# Carrier_Board.net
KiCad netlist of a schematic drawn in EAGLE
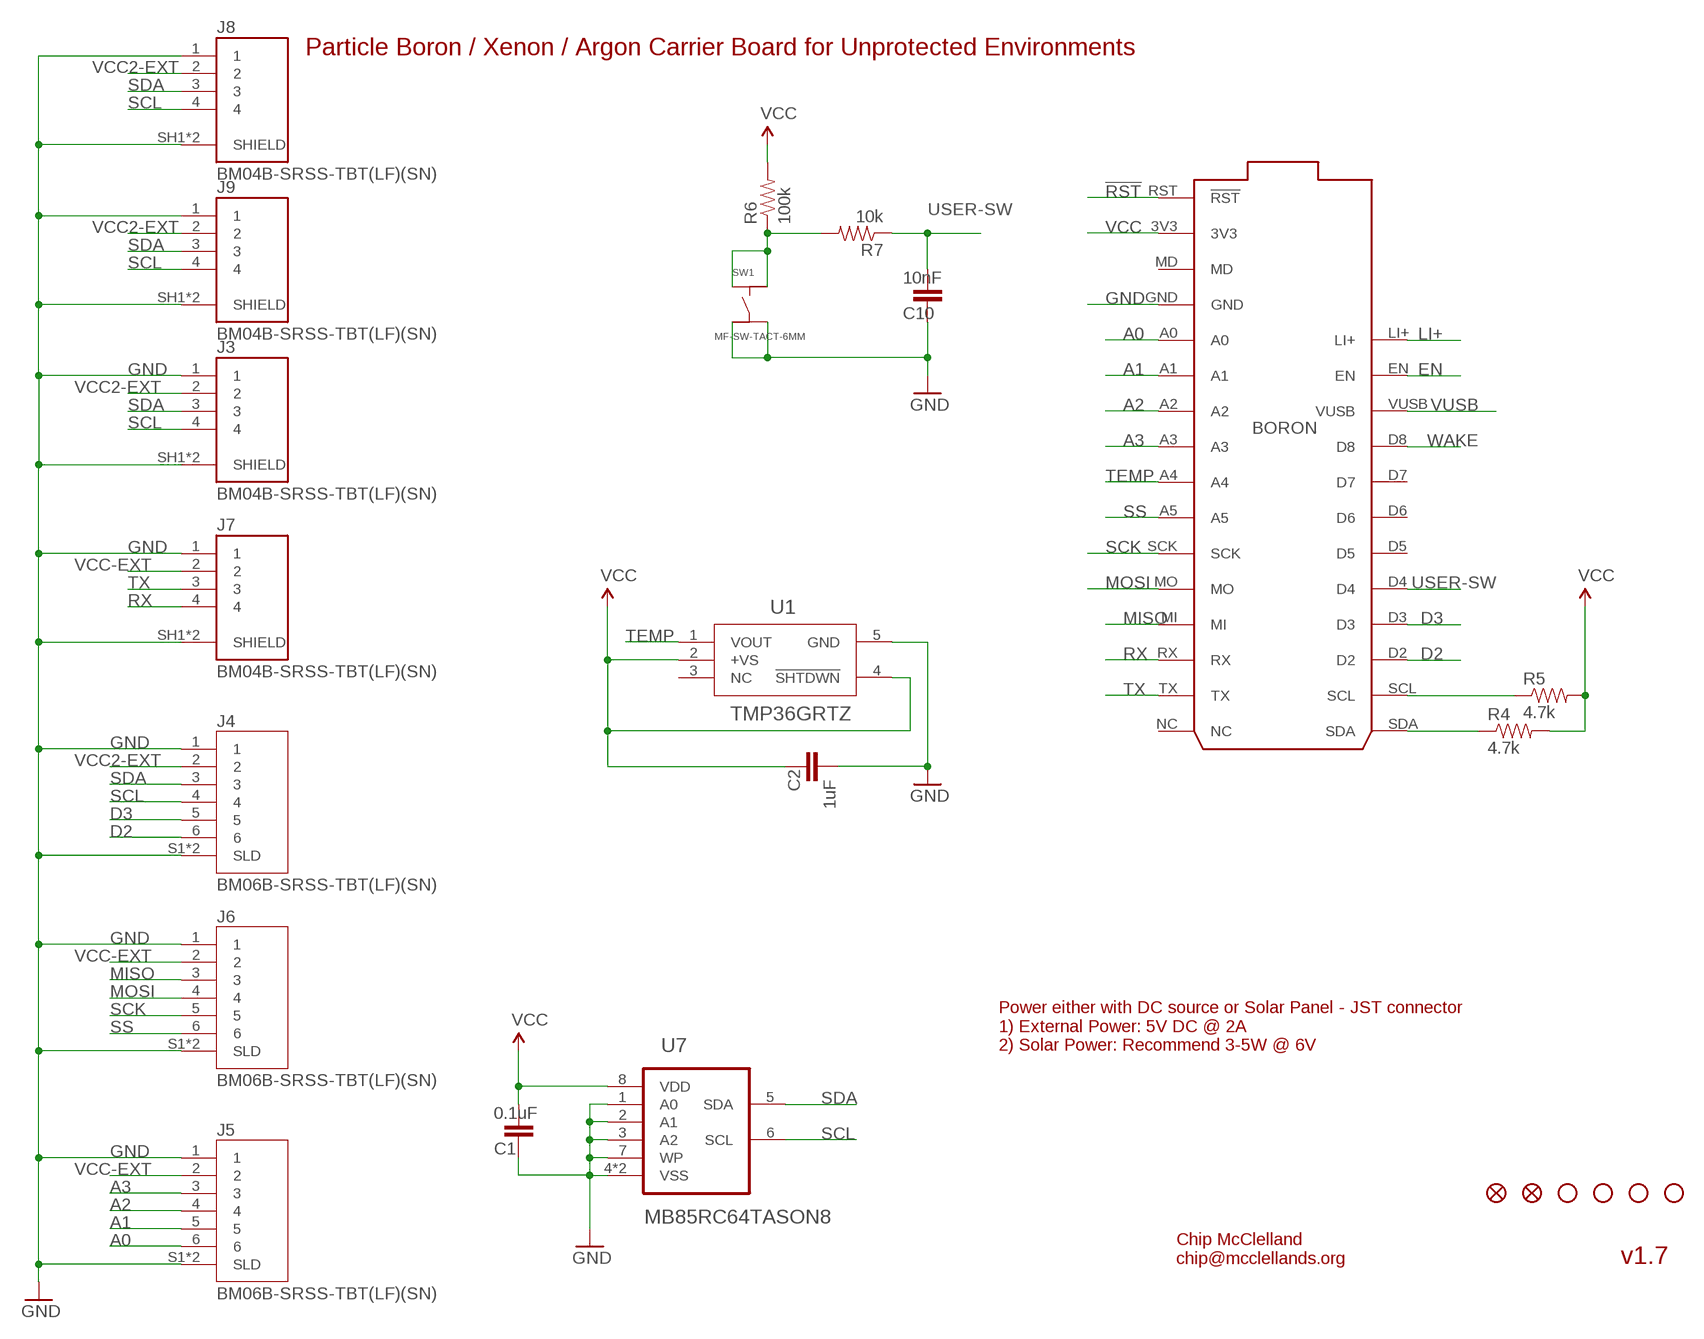
[diagram p0: schematic, sheet 1]
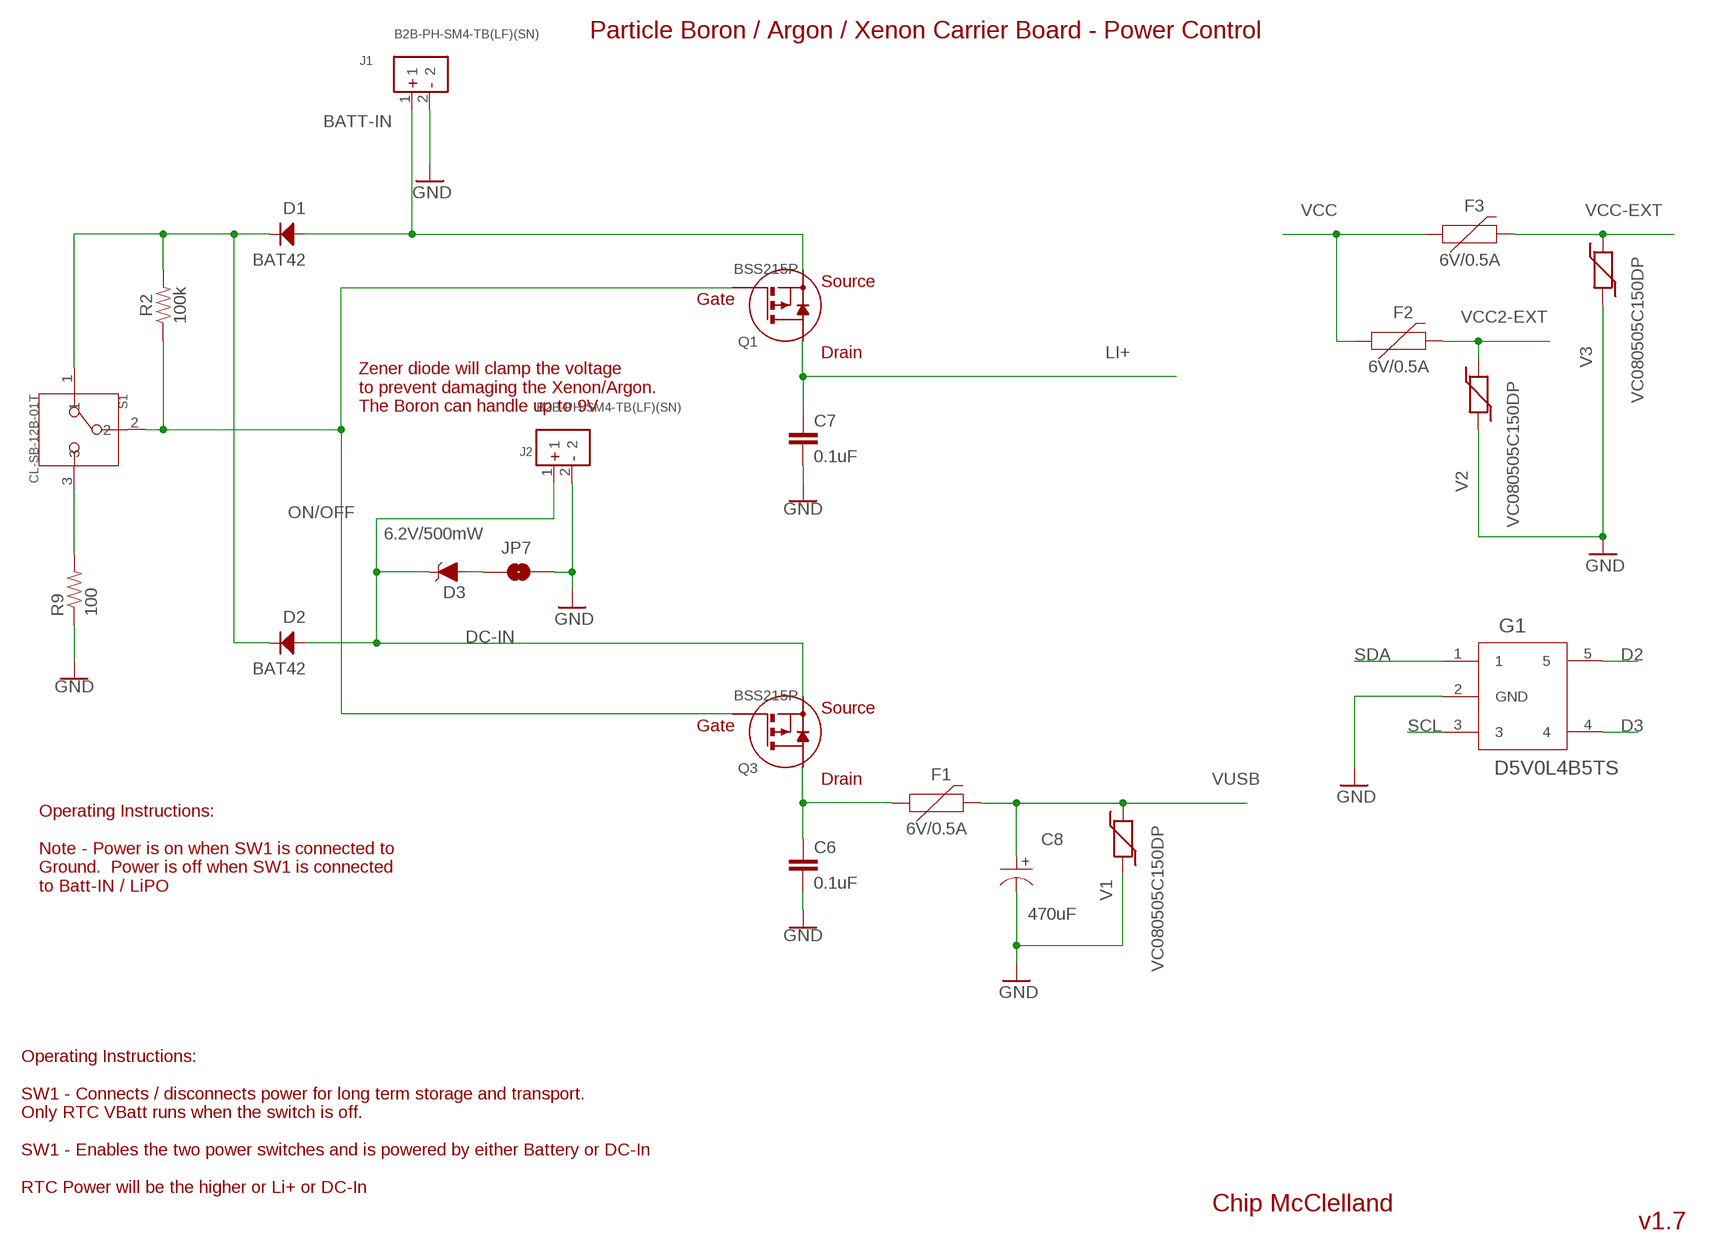
[diagram p1: schematic, sheet 2]
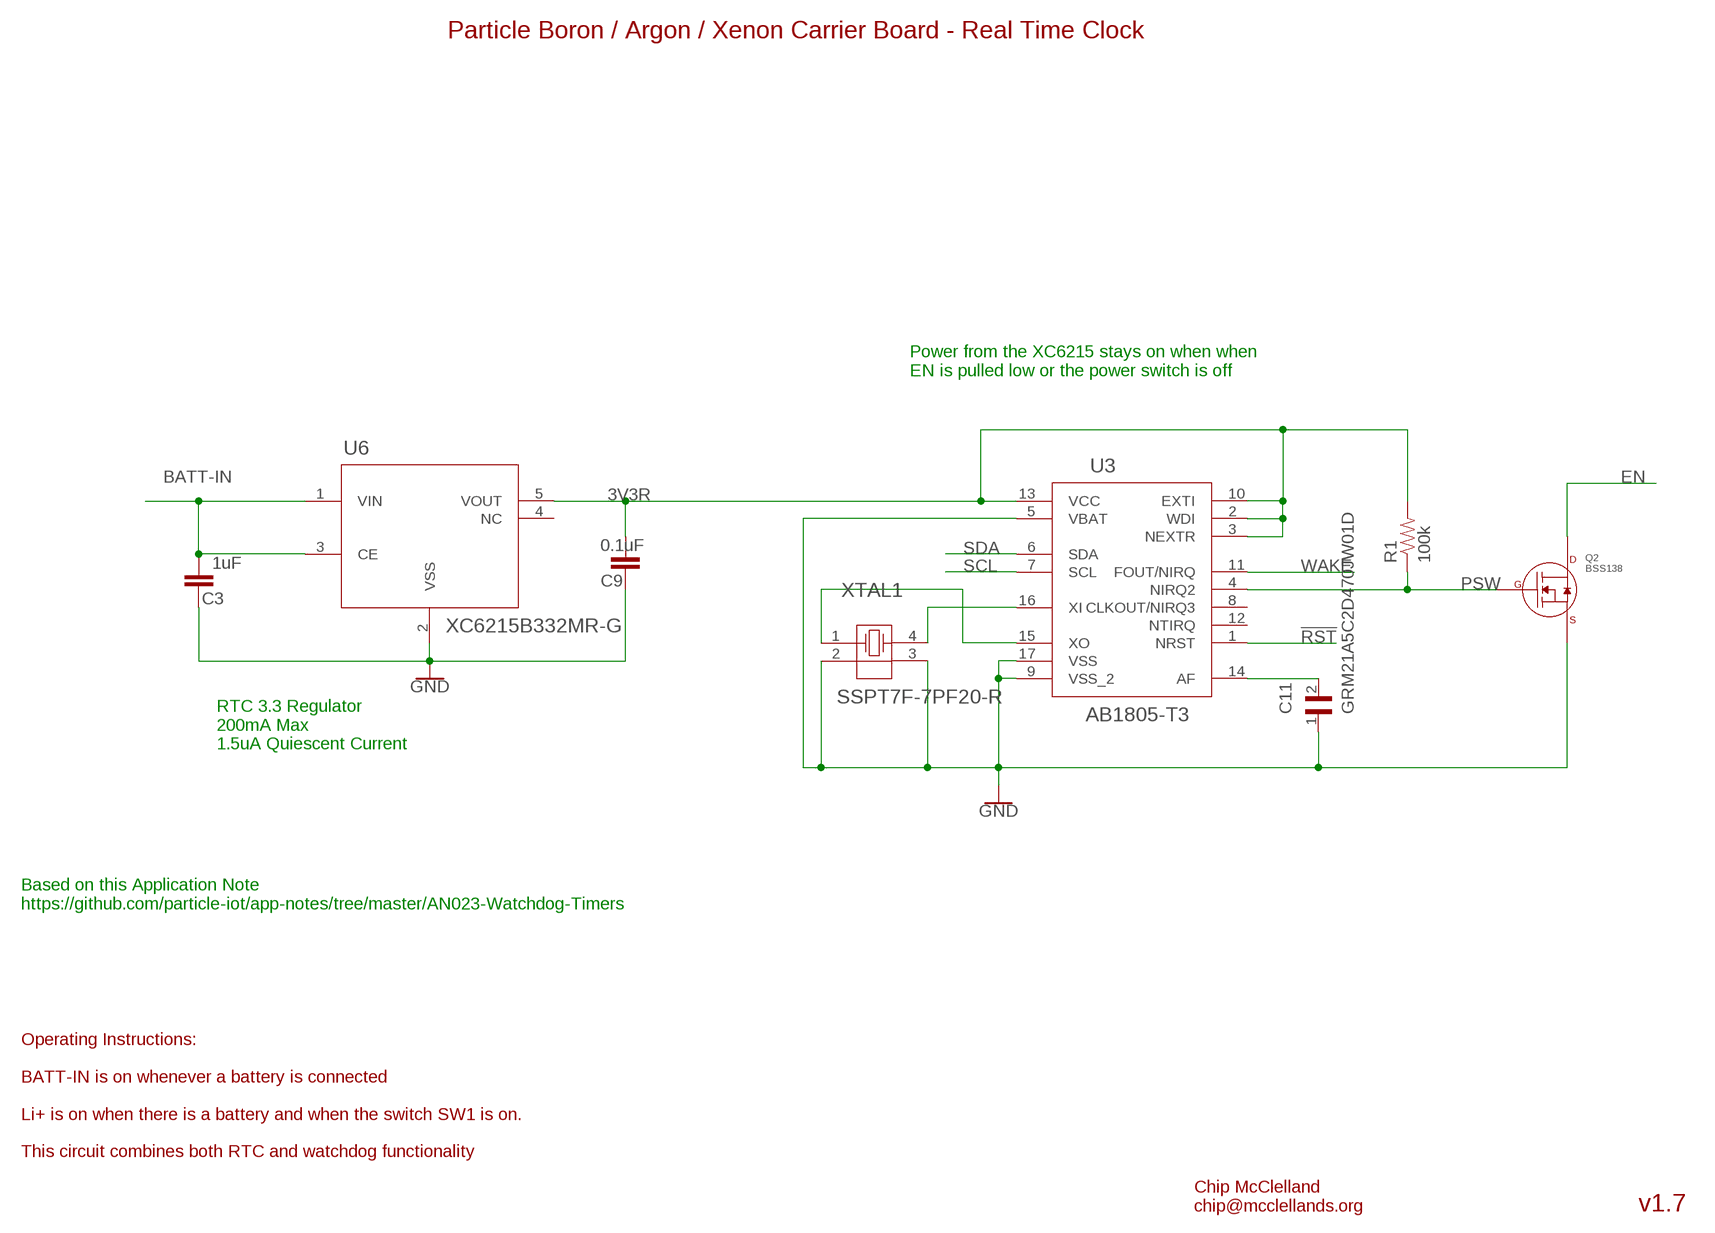
[diagram p2: schematic, sheet 3]
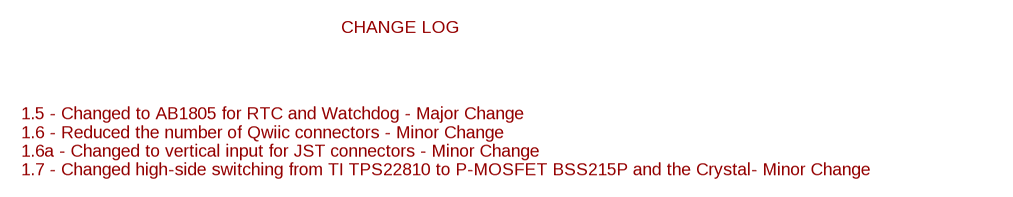
[diagram p3: schematic, sheet 4]

(export (version "E")
  (design (tool "Eeschema 10.0.6"))
  (components
    (comp (ref "C3")
      (value "1uF")
      (footprint "eagle-import:0805@1")
      (fields
        (field (name "HOUSEPART") "yes")
        (field (name "MPN") "MF-CAP-0805-1uF")
        (field (name "MPN_1") "MF-CAP-0805-1uF")
      )
      (libsource (lib "eagle-import") (part "CAP-MF-1UF-0805"))
    )
    (comp (ref "C9")
      (value "0.1uF")
      (footprint "eagle-import:0805@1")
      (fields
        (field (name "HOUSEPART") "YES")
        (field (name "MPN") "MF-CAP-0805-0.1uF")
        (field (name "HOUSEPART_1") "YES")
        (field (name "MPN_1") "MF-CAP-0805-0.1uF")
        (field (name "POPULATE") "1")
      )
      (libsource (lib "eagle-import") (part "CAP-MF-0.1UF-0805"))
    )
    (comp (ref "C11")
      (value "GRM21A5C2D470JW01D")
      (footprint "eagle-import:CAPC2012X100N")
      (fields (field (name "DIGI-KEY_PART_NUMBER") "490-14653-1-ND") (field (name "MF") "Murata"))
      (libsource (lib "eagle-import") (part "GRM21A5C2D470JW01D"))
    )
    (comp (ref "Q2")
      (value "BSS138")
      (footprint "eagle-import:SOT-23_3L_ONS")
      (fields
        (field (name "MPN") "MF-DSC-SOT233-BSS138")
        (field (name "COPYRIGHT") "Copyright (C) 2018 Accelerated Designs. All rights reserved")
      )
      (libsource (lib "eagle-import") (part "BSS138"))
    )
    (comp (ref "R1")
      (value "100k")
      (footprint "eagle-import:0805")
      (fields
        (field (name "MPN") "MF-RES-0805-100K")
        (field (name "HOUSEPART") "YES")
        (field (name "MPN_1") "MF-RES-0805-100K")
      )
      (libsource (lib "eagle-import") (part "RESISTOR-MF-100K-0805"))
    )
    (comp (ref "U3")
      (value "AB1805-T3")
      (footprint "eagle-import:QFN_16_ABR")
      (fields (field (name "MANUFACTURER") "Abracon LLC"))
      (libsource (lib "eagle-import") (part "AB1805-T3"))
    )
    (comp (ref "U6")
      (value "XC6215B332MR-G")
      (footprint "eagle-import:SOT-25_TOR")
      (libsource (lib "eagle-import") (part "XC6215B332MR-G"))
    )
    (comp (ref "XTAL1")
      (value "SSPT7F-7PF20-R")
      (footprint "eagle-import:SSP-T7-F_EPS")
      (fields (field (name "COPYRIGHT") "Copyright (C) 2018 Accelerated Designs. All rights reserved"))
      (libsource (lib "eagle-import") (part "SSPT7F-7PF20-R"))
    )
    (comp (ref "C1")
      (value "0.1uF")
      (footprint "eagle-import:0805@1")
      (fields
        (field (name "HOUSEPART") "YES")
        (field (name "MPN") "MF-CAP-0805-0.1uF")
        (field (name "HOUSEPART_1") "YES")
        (field (name "MPN_1") "MF-CAP-0805-0.1uF")
        (field (name "POPULATE") "1")
      )
      (libsource (lib "eagle-import") (part "CAP-MF-0.1UF-0805"))
    )
    (comp (ref "C2")
      (value "1uF")
      (footprint "eagle-import:0805@1")
      (fields
        (field (name "HOUSEPART") "yes")
        (field (name "MPN") "MF-CAP-0805-1uF")
        (field (name "MPN_1") "MF-CAP-0805-1uF")
      )
      (libsource (lib "eagle-import") (part "CAP-MF-1UF-0805"))
    )
    (comp (ref "C10")
      (value "10nF")
      (footprint "eagle-import:0805@1")
      (fields
        (field (name "HOUSEPART") "NO")
        (field (name "MPN") "C0805X103K1RAC3316")
        (field (name "HOUSEPART_1") "No")
        (field (name "MPN_1") "08051C103K4T2A")
        (field (name "POPULATE") "1")
      )
      (libsource (lib "eagle-import") (part "CAP-10NF-0805"))
    )
    (comp (ref "FD1")
      (value "FIDUCIALUFIDUCIAL")
      (footprint "eagle-import:FIDUCIAL-MICRO")
      (libsource (lib "eagle-import") (part "FIDUCIALUFIDUCIAL"))
    )
    (comp (ref "FD2")
      (value "FIDUCIALUFIDUCIAL")
      (footprint "eagle-import:FIDUCIAL-MICRO")
      (libsource (lib "eagle-import") (part "FIDUCIALUFIDUCIAL"))
    )
    (comp (ref "J3")
      (value "BM04B-SRSS-TBT(LF)(SN)")
      (footprint "eagle-import:CONN_BM04B-SRSS-TBT(LF)(SN)")
      (fields (field (name "MF") "JST Sales"))
      (libsource (lib "eagle-import") (part "BM04B-SRSS-TBT(LF)(SN)"))
    )
    (comp (ref "J4")
      (value "BM06B-SRSS-TBT(LF)(SN)")
      (footprint "eagle-import:JST_BM06B-SRSS-TB(LF)(SN)")
      (libsource (lib "eagle-import") (part "BM06B-SRSS-TBT(LF)(SN)"))
    )
    (comp (ref "J5")
      (value "BM06B-SRSS-TBT(LF)(SN)")
      (footprint "eagle-import:JST_BM06B-SRSS-TB(LF)(SN)")
      (libsource (lib "eagle-import") (part "BM06B-SRSS-TBT(LF)(SN)"))
    )
    (comp (ref "J6")
      (value "BM06B-SRSS-TBT(LF)(SN)")
      (footprint "eagle-import:JST_BM06B-SRSS-TB(LF)(SN)")
      (libsource (lib "eagle-import") (part "BM06B-SRSS-TBT(LF)(SN)"))
    )
    (comp (ref "J7")
      (value "BM04B-SRSS-TBT(LF)(SN)")
      (footprint "eagle-import:CONN_BM04B-SRSS-TBT(LF)(SN)")
      (fields (field (name "MF") "JST Sales"))
      (libsource (lib "eagle-import") (part "BM04B-SRSS-TBT(LF)(SN)"))
    )
    (comp (ref "J8")
      (value "BM04B-SRSS-TBT(LF)(SN)")
      (footprint "eagle-import:CONN_BM04B-SRSS-TBT(LF)(SN)")
      (fields (field (name "MF") "JST Sales"))
      (libsource (lib "eagle-import") (part "BM04B-SRSS-TBT(LF)(SN)"))
    )
    (comp (ref "J9")
      (value "BM04B-SRSS-TBT(LF)(SN)")
      (footprint "eagle-import:CONN_BM04B-SRSS-TBT(LF)(SN)")
      (fields (field (name "MF") "JST Sales"))
      (libsource (lib "eagle-import") (part "BM04B-SRSS-TBT(LF)(SN)"))
    )
    (comp (ref "JP3")
      (value "STAND-OFF")
      (footprint "eagle-import:STAND-OFF")
      (libsource (lib "eagle-import") (part "STAND-OFF"))
    )
    (comp (ref "JP4")
      (value "STAND-OFF")
      (footprint "eagle-import:STAND-OFF")
      (libsource (lib "eagle-import") (part "STAND-OFF"))
    )
    (comp (ref "JP5")
      (value "STAND-OFF")
      (footprint "eagle-import:STAND-OFF")
      (libsource (lib "eagle-import") (part "STAND-OFF"))
    )
    (comp (ref "JP6")
      (value "STAND-OFF")
      (footprint "eagle-import:STAND-OFF")
      (libsource (lib "eagle-import") (part "STAND-OFF"))
    )
    (comp (ref "P1")
      (value "Particle Boron / Xenon / Argon")
      (footprint "eagle-import:PARTICLE-DEVICES_BORON")
      (libsource (lib "eagle-import") (part "PARTICLE-DEVICES-BORON"))
    )
    (comp (ref "R4")
      (value "4.7k")
      (footprint "eagle-import:0805")
      (fields
        (field (name "HOUSEPART") "1")
        (field (name "MPN") "MF-RES-0805-4.7K")
        (field (name "MPN_1") "MF-RES-0805-4.7K")
      )
      (libsource (lib "eagle-import") (part "RESISTOR-MF-4.7K-0805"))
    )
    (comp (ref "R5")
      (value "4.7k")
      (footprint "eagle-import:0805")
      (fields
        (field (name "HOUSEPART") "1")
        (field (name "MPN") "MF-RES-0805-4.7K")
        (field (name "MPN_1") "MF-RES-0805-4.7K")
      )
      (libsource (lib "eagle-import") (part "RESISTOR-MF-4.7K-0805"))
    )
    (comp (ref "R6")
      (value "100k")
      (footprint "eagle-import:0805")
      (fields
        (field (name "MPN") "MF-RES-0805-100K")
        (field (name "HOUSEPART") "YES")
        (field (name "MPN_1") "MF-RES-0805-100K")
      )
      (libsource (lib "eagle-import") (part "RESISTOR-MF-100K-0805"))
    )
    (comp (ref "R7")
      (value "10k")
      (footprint "eagle-import:0805")
      (fields
        (field (name "MPN") "MF-RES-0805-10K")
        (field (name "HOUSEPART") "YES")
        (field (name "MPN_1") "MF-RES-0805-10K")
      )
      (libsource (lib "eagle-import") (part "RESISTOR-MF-10K-0805"))
    )
    (comp (ref "SW1")
      (value "MF-SW-TACT-6MM")
      (footprint "eagle-import:TACT6MM")
      (fields (field (name "HOUSEPART") "YES"))
      (libsource (lib "eagle-import") (part "TACT_6MM"))
    )
    (comp (ref "U1")
      (value "TMP36GRTZ")
      (footprint "eagle-import:RJ_5_ADI")
      (fields
        (field (name "MANUFACTURER_PART_NUMBER") "TMP36GRTZ-REEL7")
        (field (name "MANUFACTURER_PART_NUMBER_1") "TMP36GRTZ-REEL7")
      )
      (libsource (lib "eagle-import") (part "TMP36GRTZ-REEL7"))
    )
    (comp (ref "U7")
      (value "MB85RC64TASON8")
      (footprint "eagle-import:SON50P200X300X75-9N")
      (libsource (lib "eagle-import") (part "MB85RC64TASON8"))
    )
    (comp (ref "C6")
      (value "0.1uF")
      (footprint "eagle-import:0805@1")
      (fields
        (field (name "HOUSEPART") "YES")
        (field (name "MPN") "MF-CAP-0805-0.1uF")
        (field (name "HOUSEPART_1") "Yes")
        (field (name "MPN_1") "MF-CAP-0805-0.1uF")
      )
      (libsource (lib "eagle-import") (part "CAP-MF-0.1UF-0805"))
    )
    (comp (ref "C7")
      (value "0.1uF")
      (footprint "eagle-import:0805@1")
      (fields
        (field (name "HOUSEPART") "YES")
        (field (name "MPN") "MF-CAP-0805-0.1uF")
        (field (name "HOUSEPART_1") "Yes")
        (field (name "MPN_1") "MF-CAP-0805-0.1uF")
      )
      (libsource (lib "eagle-import") (part "CAP-MF-0.1UF-0805"))
    )
    (comp (ref "C8")
      (value "470uF")
      (footprint "eagle-import:CP10MM")
      (fields (field (name "HOUSEPART") "1") (field (name "MPN") "MF-CAP-10MM-470uF"))
      (libsource (lib "eagle-import") (part "CAPACITOR_P_10MM"))
    )
    (comp (ref "D1")
      (value "BAT42")
      (footprint "eagle-import:SOD-123")
      (fields (field (name "HOUSEPART") "YES") (field (name "MPN") "MF-DIO-SOD123-BAT42"))
      (libsource (lib "eagle-import") (part "DIODES_SOD-123_BAT42"))
    )
    (comp (ref "D2")
      (value "BAT42")
      (footprint "eagle-import:SOD-123")
      (fields (field (name "HOUSEPART") "YES") (field (name "MPN") "MF-DIO-SOD123-BAT42"))
      (libsource (lib "eagle-import") (part "DIODES_SOD-123_BAT42"))
    )
    (comp (ref "D3")
      (value "6.2V/500mW")
      (footprint "eagle-import:PANASONIC_SMINI2-F5-B")
      (fields (field (name "MPN") "TDZ6V2J,115"))
      (libsource (lib "eagle-import") (part "DIODE-ZENER-DZ2J150M0L"))
    )
    (comp (ref "F1")
      (value "6V/0.5A")
      (footprint "eagle-import:1206")
      (fields (field (name "MPN") "046801.5NR"))
      (libsource (lib "eagle-import") (part "PPTC_HALF-AMP"))
    )
    (comp (ref "F2")
      (value "6V/0.5A")
      (footprint "eagle-import:1206")
      (fields (field (name "MPN") "0466.500NR"))
      (libsource (lib "eagle-import") (part "PPTC_HALF-AMP"))
    )
    (comp (ref "F3")
      (value "6V/0.5A")
      (footprint "eagle-import:1206")
      (fields (field (name "MPN") "0466.500NR"))
      (libsource (lib "eagle-import") (part "PPTC_HALF-AMP"))
    )
    (comp (ref "G1")
      (value "D5V0L4B5TS")
      (footprint "eagle-import:SOT-23-5")
      (fields (field (name "MPN") "D5V0L4B5TS-7"))
      (libsource (lib "eagle-import") (part "D5V0L4B5TS"))
    )
    (comp (ref "J1")
      (value "B2B-PH-SM4-TB(LF)(SN)")
      (footprint "eagle-import:JST_B2B-PH-SM4-TB(LF)(SN)")
      (fields (field (name "DIGI-KEY_PART_NUMBER") "455-1734-1-ND") (field (name "MF") "JST Sales"))
      (libsource (lib "eagle-import") (part "B2B-PH-SM4-TB(LF)(SN)"))
    )
    (comp (ref "J2")
      (value "B2B-PH-SM4-TB(LF)(SN)")
      (footprint "eagle-import:JST_B2B-PH-SM4-TB(LF)(SN)")
      (fields (field (name "DIGI-KEY_PART_NUMBER") "455-1734-1-ND") (field (name "MF") "JST Sales"))
      (libsource (lib "eagle-import") (part "B2B-PH-SM4-TB(LF)(SN)"))
    )
    (comp (ref "JP7")
      (value "JUMPER-SMT_2_NO_SILK")
      (footprint "eagle-import:SMT-JUMPER_2_NO_SILK")
      (libsource (lib "eagle-import") (part "JUMPER-SMT_2_NO_SILK"))
    )
    (comp (ref "Q1")
      (value "BSS215P")
      (footprint "eagle-import:SOT-23_3L_ONS-M")
      (fields (field (name "HOUSEPART") "No") (field (name "MPN") "BSS215PH6327XTSA1"))
      (libsource (lib "eagle-import") (part "BSS215P"))
    )
    (comp (ref "Q3")
      (value "BSS215P")
      (footprint "eagle-import:SOT-23_3L_ONS-M")
      (fields (field (name "HOUSEPART") "No") (field (name "MPN") "BSS215PH6327XTSA1"))
      (libsource (lib "eagle-import") (part "BSS215P"))
    )
    (comp (ref "R2")
      (value "100k")
      (footprint "eagle-import:0805")
      (fields (field (name "MPN") "MF-RES-0805-100K"))
      (libsource (lib "eagle-import") (part "RESISTOR-MF-100K-0805"))
    )
    (comp (ref "R9")
      (value "100")
      (footprint "eagle-import:0805")
      (fields
        (field (name "HOUSEPART") "YES")
        (field (name "MPN") "MF-RES-0805-100")
        (field (name "HOUSEPART_1") "Yes")
        (field (name "MPN_1") "MF-RES-0805-100")
      )
      (libsource (lib "eagle-import") (part "RESISTOR-MF-100-0805"))
    )
    (comp (ref "S1")
      (value "CL-SB-12B-01T")
      (footprint "eagle-import:CL-SB-12B")
      (fields (field (name "DIGI-KEY_PART_NUMBER") "563-1318-1-ND") (field (name "MF") "Nidec Copal"))
      (libsource (lib "eagle-import") (part "CL-SB-12B-01T"))
    )
    (comp (ref "V1")
      (value "VC080505C150DP")
      (footprint "eagle-import:0805")
      (libsource (lib "eagle-import") (part "VARISTOR"))
    )
    (comp (ref "V2")
      (value "VC080505C150DP")
      (footprint "eagle-import:0805")
      (libsource (lib "eagle-import") (part "VARISTOR"))
    )
    (comp (ref "V3")
      (value "VC080505C150DP")
      (footprint "eagle-import:0805")
      (libsource (lib "eagle-import") (part "VARISTOR"))
    )
  )
  (nets
    (net (code "1") (name "3V3R") (class "Default")
      (node (ref "C9") (pin "1") (pinfunction "1_1") (pintype "passive"))
      (node (ref "R1") (pin "2") (pinfunction "2_2") (pintype "passive"))
      (node (ref "U3") (pin "10") (pinfunction "EXTI_10") (pintype "input"))
      (node (ref "U3") (pin "13") (pinfunction "VCC_13") (pintype "power_in"))
      (node (ref "U3") (pin "2") (pinfunction "WDI_2") (pintype "input"))
      (node (ref "U3") (pin "3") (pinfunction "NEXTR_3") (pintype "input"))
      (node (ref "U6") (pin "5") (pinfunction "VOUT_5") (pintype "output"))
    )
    (net (code "2") (name "A0") (class "Default")
      (node (ref "J5") (pin "6") (pinfunction "6_6") (pintype "passive"))
      (node (ref "P1") (pin "A0") (pinfunction "A0_A0") (pintype "bidirectional"))
    )
    (net (code "3") (name "A1") (class "Default")
      (node (ref "J5") (pin "5") (pinfunction "5_5") (pintype "passive"))
      (node (ref "P1") (pin "A1") (pinfunction "A1_A1") (pintype "bidirectional"))
    )
    (net (code "4") (name "A2") (class "Default")
      (node (ref "J5") (pin "4") (pinfunction "4_4") (pintype "passive"))
      (node (ref "P1") (pin "A2") (pinfunction "A2_A2") (pintype "bidirectional"))
    )
    (net (code "5") (name "A3") (class "Default")
      (node (ref "J5") (pin "3") (pinfunction "3_3") (pintype "passive"))
      (node (ref "P1") (pin "A3") (pinfunction "A3_A3") (pintype "bidirectional"))
    )
    (net (code "6") (name "BATT-IN") (class "Default")
      (node (ref "C3") (pin "2") (pinfunction "2_2") (pintype "passive"))
      (node (ref "D1") (pin "ANODE") (pinfunction "ANODE_ANODE") (pintype "bidirectional"))
      (node (ref "J1") (pin "1") (pinfunction "1_1") (pintype "passive"))
      (node (ref "Q1") (pin "2") (pinfunction "SOURCE_2") (pintype "passive"))
      (node (ref "U6") (pin "1") (pinfunction "VIN_1") (pintype "power_in"))
      (node (ref "U6") (pin "3") (pinfunction "CE_3") (pintype "passive"))
    )
    (net (code "7") (name "D2") (class "Default")
      (node (ref "G1") (pin "5") (pinfunction "5_5") (pintype "output"))
      (node (ref "J4") (pin "6") (pinfunction "6_6") (pintype "passive"))
      (node (ref "P1") (pin "D2") (pinfunction "D2_D2") (pintype "bidirectional"))
    )
    (net (code "8") (name "D3") (class "Default")
      (node (ref "G1") (pin "4") (pinfunction "4_4") (pintype "output"))
      (node (ref "J4") (pin "5") (pinfunction "5_5") (pintype "passive"))
      (node (ref "P1") (pin "D3") (pinfunction "D3_D3") (pintype "bidirectional"))
    )
    (net (code "9") (name "DC-IN") (class "Default")
      (node (ref "D2") (pin "ANODE") (pinfunction "ANODE_ANODE") (pintype "bidirectional"))
      (node (ref "D3") (pin "C") (pinfunction "C_C") (pintype "passive"))
      (node (ref "J2") (pin "1") (pinfunction "1_1") (pintype "passive"))
      (node (ref "Q3") (pin "2") (pinfunction "SOURCE_2") (pintype "passive"))
    )
    (net (code "10") (name "EN") (class "Default")
      (node (ref "P1") (pin "EN") (pinfunction "EN_EN") (pintype "bidirectional"))
      (node (ref "Q2") (pin "3") (pinfunction "DRAIN_3") (pintype "bidirectional"))
    )
    (net (code "11") (name "GND") (class "Default")
      (node (ref "C1") (pin "2") (pinfunction "2_2") (pintype "passive"))
      (node (ref "C10") (pin "2") (pinfunction "2_2") (pintype "passive"))
      (node (ref "C11") (pin "1") (pinfunction "1_1") (pintype "passive"))
      (node (ref "C2") (pin "2") (pinfunction "2_2") (pintype "passive"))
      (node (ref "C3") (pin "1") (pinfunction "1_1") (pintype "passive"))
      (node (ref "C6") (pin "2") (pinfunction "2_2") (pintype "passive"))
      (node (ref "C7") (pin "2") (pinfunction "2_2") (pintype "passive"))
      (node (ref "C8") (pin "P$2") (pinfunction "P$2_P$2") (pintype "passive"))
      (node (ref "C9") (pin "2") (pinfunction "2_2") (pintype "passive"))
      (node (ref "G1") (pin "2") (pinfunction "GND_2") (pintype "power_in"))
      (node (ref "J1") (pin "2") (pinfunction "2_2") (pintype "passive"))
      (node (ref "J2") (pin "2") (pinfunction "2_2") (pintype "passive"))
      (node (ref "J3") (pin "1") (pinfunction "1_1") (pintype "passive"))
      (node (ref "J3") (pin "SH1") (pinfunction "SHIELD_SH1") (pintype "passive"))
      (node (ref "J3") (pin "SH2") (pinfunction "SHIELD_SH2") (pintype "passive"))
      (node (ref "J4") (pin "1") (pinfunction "1_1") (pintype "passive"))
      (node (ref "J4") (pin "S1") (pinfunction "SLD_S1") (pintype "passive"))
      (node (ref "J4") (pin "S2") (pinfunction "SLD_S2") (pintype "passive"))
      (node (ref "J5") (pin "1") (pinfunction "1_1") (pintype "passive"))
      (node (ref "J5") (pin "S1") (pinfunction "SLD_S1") (pintype "passive"))
      (node (ref "J5") (pin "S2") (pinfunction "SLD_S2") (pintype "passive"))
      (node (ref "J6") (pin "1") (pinfunction "1_1") (pintype "passive"))
      (node (ref "J6") (pin "S1") (pinfunction "SLD_S1") (pintype "passive"))
      (node (ref "J6") (pin "S2") (pinfunction "SLD_S2") (pintype "passive"))
      (node (ref "J7") (pin "1") (pinfunction "1_1") (pintype "passive"))
      (node (ref "J7") (pin "SH1") (pinfunction "SHIELD_SH1") (pintype "passive"))
      (node (ref "J7") (pin "SH2") (pinfunction "SHIELD_SH2") (pintype "passive"))
      (node (ref "J8") (pin "1") (pinfunction "1_1") (pintype "passive"))
      (node (ref "J8") (pin "SH1") (pinfunction "SHIELD_SH1") (pintype "passive"))
      (node (ref "J8") (pin "SH2") (pinfunction "SHIELD_SH2") (pintype "passive"))
      (node (ref "J9") (pin "1") (pinfunction "1_1") (pintype "passive"))
      (node (ref "J9") (pin "SH1") (pinfunction "SHIELD_SH1") (pintype "passive"))
      (node (ref "J9") (pin "SH2") (pinfunction "SHIELD_SH2") (pintype "passive"))
      (node (ref "JP7") (pin "1") (pinfunction "1_1") (pintype "passive"))
      (node (ref "P1") (pin "GND") (pinfunction "GND_GND") (pintype "bidirectional"))
      (node (ref "Q2") (pin "2") (pinfunction "SOURCE_2") (pintype "bidirectional"))
      (node (ref "R9") (pin "1") (pinfunction "1_1") (pintype "passive"))
      (node (ref "SW1") (pin "P$3") (pinfunction "P$3_P$3") (pintype "bidirectional"))
      (node (ref "SW1") (pin "P$4") (pinfunction "P$4_P$4") (pintype "bidirectional"))
      (node (ref "U1") (pin "5") (pinfunction "GND_5") (pintype "passive"))
      (node (ref "U3") (pin "17") (pinfunction "VSS_17") (pintype "power_in"))
      (node (ref "U3") (pin "5") (pinfunction "VBAT_5") (pintype "power_in"))
      (node (ref "U3") (pin "9") (pinfunction "VSS_2_9") (pintype "power_in"))
      (node (ref "U6") (pin "2") (pinfunction "VSS_2") (pintype "passive"))
      (node (ref "U7") (pin "1") (pinfunction "A0_1") (pintype "input"))
      (node (ref "U7") (pin "2") (pinfunction "A1_2") (pintype "input"))
      (node (ref "U7") (pin "3") (pinfunction "A2_3") (pintype "input"))
      (node (ref "U7") (pin "4") (pinfunction "VSS_4") (pintype "passive"))
      (node (ref "U7") (pin "7") (pinfunction "WP_7") (pintype "input"))
      (node (ref "U7") (pin "9") (pinfunction "VSS_9") (pintype "passive"))
      (node (ref "V1") (pin "1") (pinfunction "1_1") (pintype "passive"))
      (node (ref "V2") (pin "1") (pinfunction "1_1") (pintype "passive"))
      (node (ref "V3") (pin "1") (pinfunction "1_1") (pintype "passive"))
      (node (ref "XTAL1") (pin "2") (pinfunction "2_2") (pintype "passive"))
      (node (ref "XTAL1") (pin "3") (pinfunction "3_3") (pintype "passive"))
    )
    (net (code "12") (name "LI+") (class "Default")
      (node (ref "C7") (pin "1") (pinfunction "1_1") (pintype "passive"))
      (node (ref "P1") (pin "LI+") (pinfunction "LI+_LI+") (pintype "bidirectional"))
      (node (ref "Q1") (pin "3") (pinfunction "DRAIN_3") (pintype "passive"))
    )
    (net (code "13") (name "MISO") (class "Default")
      (node (ref "J6") (pin "3") (pinfunction "3_3") (pintype "passive"))
      (node (ref "P1") (pin "MI") (pinfunction "MI_MI") (pintype "bidirectional"))
    )
    (net (code "14") (name "MOSI") (class "Default")
      (node (ref "J6") (pin "4") (pinfunction "4_4") (pintype "passive"))
      (node (ref "P1") (pin "MO") (pinfunction "MO_MO") (pintype "bidirectional"))
    )
    (net (code "15") (name "Net-(D1-PadCATHODE)") (class "Default")
      (node (ref "D1") (pin "CATHODE") (pinfunction "CATHODE_CATHODE") (pintype "bidirectional"))
      (node (ref "D2") (pin "CATHODE") (pinfunction "CATHODE_CATHODE") (pintype "bidirectional"))
      (node (ref "R2") (pin "2") (pinfunction "2_2") (pintype "passive"))
      (node (ref "S1") (pin "1") (pinfunction "1_1") (pintype "bidirectional"))
    )
    (net (code "16") (name "Net-(D3-PadA)") (class "Default")
      (node (ref "D3") (pin "A") (pinfunction "A_A") (pintype "passive"))
      (node (ref "JP7") (pin "2") (pinfunction "2_2") (pintype "passive"))
    )
    (net (code "17") (name "Net-(Q3-DRAIN)") (class "Default")
      (node (ref "C6") (pin "1") (pinfunction "1_1") (pintype "passive"))
      (node (ref "F1") (pin "1") (pinfunction "1_1") (pintype "bidirectional"))
      (node (ref "Q3") (pin "3") (pinfunction "DRAIN_3") (pintype "passive"))
    )
    (net (code "18") (name "Net-(R6-Pad1)") (class "Default")
      (node (ref "R6") (pin "1") (pinfunction "1_1") (pintype "passive"))
      (node (ref "R7") (pin "2") (pinfunction "2_2") (pintype "passive"))
      (node (ref "SW1") (pin "P$1") (pinfunction "P$1_P$1") (pintype "bidirectional"))
      (node (ref "SW1") (pin "P$2") (pinfunction "P$2_P$2") (pintype "bidirectional"))
    )
    (net (code "19") (name "Net-(R9-Pad2)") (class "Default")
      (node (ref "R9") (pin "2") (pinfunction "2_2") (pintype "passive"))
      (node (ref "S1") (pin "3") (pinfunction "3_3") (pintype "bidirectional"))
    )
    (net (code "20") (name "Net-(U3-AF)") (class "Default")
      (node (ref "C11") (pin "2") (pinfunction "2_2") (pintype "passive"))
      (node (ref "U3") (pin "14") (pinfunction "AF_14") (pintype "output"))
    )
    (net (code "21") (name "Net-(U3-XI)") (class "Default")
      (node (ref "U3") (pin "16") (pinfunction "XI_16") (pintype "input"))
      (node (ref "XTAL1") (pin "4") (pinfunction "4_4") (pintype "passive"))
    )
    (net (code "22") (name "Net-(U3-XO)") (class "Default")
      (node (ref "U3") (pin "15") (pinfunction "XO_15") (pintype "output"))
      (node (ref "XTAL1") (pin "1") (pinfunction "1_1") (pintype "passive"))
    )
    (net (code "23") (name "ON{slash}OFF") (class "Default")
      (node (ref "Q1") (pin "1") (pinfunction "GATE_1") (pintype "passive"))
      (node (ref "Q3") (pin "1") (pinfunction "GATE_1") (pintype "passive"))
      (node (ref "R2") (pin "1") (pinfunction "1_1") (pintype "passive"))
      (node (ref "S1") (pin "2") (pinfunction "2_2") (pintype "bidirectional"))
    )
    (net (code "24") (name "PSW") (class "Default")
      (node (ref "Q2") (pin "1") (pinfunction "GATE_1") (pintype "bidirectional"))
      (node (ref "R1") (pin "1") (pinfunction "1_1") (pintype "passive"))
      (node (ref "U3") (pin "4") (pinfunction "NIRQ2_4") (pintype "output"))
    )
    (net (code "25") (name "RX") (class "Default")
      (node (ref "J7") (pin "4") (pinfunction "4_4") (pintype "passive"))
      (node (ref "P1") (pin "RX") (pinfunction "RX_RX") (pintype "bidirectional"))
    )
    (net (code "26") (name "SCK") (class "Default")
      (node (ref "J6") (pin "5") (pinfunction "5_5") (pintype "passive"))
      (node (ref "P1") (pin "SCK") (pinfunction "SCK_SCK") (pintype "bidirectional"))
    )
    (net (code "27") (name "SCL") (class "Default")
      (node (ref "G1") (pin "3") (pinfunction "3_3") (pintype "input"))
      (node (ref "J3") (pin "4") (pinfunction "4_4") (pintype "passive"))
      (node (ref "J4") (pin "4") (pinfunction "4_4") (pintype "passive"))
      (node (ref "J8") (pin "4") (pinfunction "4_4") (pintype "passive"))
      (node (ref "J9") (pin "4") (pinfunction "4_4") (pintype "passive"))
      (node (ref "P1") (pin "SCL") (pinfunction "SCL_SCL") (pintype "bidirectional"))
      (node (ref "R5") (pin "1") (pinfunction "1_1") (pintype "passive"))
      (node (ref "U3") (pin "7") (pinfunction "SCL_7") (pintype "input"))
      (node (ref "U7") (pin "6") (pinfunction "SCL_6") (pintype "input"))
    )
    (net (code "28") (name "SDA") (class "Default")
      (node (ref "G1") (pin "1") (pinfunction "1_1") (pintype "input"))
      (node (ref "J3") (pin "3") (pinfunction "3_3") (pintype "passive"))
      (node (ref "J4") (pin "3") (pinfunction "3_3") (pintype "passive"))
      (node (ref "J8") (pin "3") (pinfunction "3_3") (pintype "passive"))
      (node (ref "J9") (pin "3") (pinfunction "3_3") (pintype "passive"))
      (node (ref "P1") (pin "SDA") (pinfunction "SDA_SDA") (pintype "bidirectional"))
      (node (ref "R4") (pin "1") (pinfunction "1_1") (pintype "passive"))
      (node (ref "U3") (pin "6") (pinfunction "SDA_6") (pintype "bidirectional"))
      (node (ref "U7") (pin "5") (pinfunction "SDA_5") (pintype "bidirectional"))
    )
    (net (code "29") (name "SS") (class "Default")
      (node (ref "J6") (pin "6") (pinfunction "6_6") (pintype "passive"))
      (node (ref "P1") (pin "A5") (pinfunction "A5_A5") (pintype "bidirectional"))
    )
    (net (code "30") (name "TEMP") (class "Default")
      (node (ref "P1") (pin "A4") (pinfunction "A4_A4") (pintype "bidirectional"))
      (node (ref "U1") (pin "1") (pinfunction "VOUT_1") (pintype "passive"))
    )
    (net (code "31") (name "TX") (class "Default")
      (node (ref "J7") (pin "3") (pinfunction "3_3") (pintype "passive"))
      (node (ref "P1") (pin "TX") (pinfunction "TX_TX") (pintype "bidirectional"))
    )
    (net (code "32") (name "USER-SW") (class "Default")
      (node (ref "C10") (pin "1") (pinfunction "1_1") (pintype "passive"))
      (node (ref "P1") (pin "D4") (pinfunction "D4_D4") (pintype "bidirectional"))
      (node (ref "R7") (pin "1") (pinfunction "1_1") (pintype "passive"))
    )
    (net (code "33") (name "VCC") (class "Default")
      (node (ref "C1") (pin "1") (pinfunction "1_1") (pintype "passive"))
      (node (ref "C2") (pin "1") (pinfunction "1_1") (pintype "passive"))
      (node (ref "F2") (pin "1") (pinfunction "1_1") (pintype "bidirectional"))
      (node (ref "F3") (pin "1") (pinfunction "1_1") (pintype "bidirectional"))
      (node (ref "P1") (pin "3V3") (pinfunction "3V3_3V3") (pintype "bidirectional"))
      (node (ref "R4") (pin "2") (pinfunction "2_2") (pintype "passive"))
      (node (ref "R5") (pin "2") (pinfunction "2_2") (pintype "passive"))
      (node (ref "R6") (pin "2") (pinfunction "2_2") (pintype "passive"))
      (node (ref "U1") (pin "2") (pinfunction "+VS_2") (pintype "power_in"))
      (node (ref "U1") (pin "4") (pinfunction "~{SHTDWN}_4") (pintype "passive"))
      (node (ref "U7") (pin "8") (pinfunction "VDD_8") (pintype "power_in"))
    )
    (net (code "34") (name "VCC-EXT") (class "Default")
      (node (ref "F3") (pin "2") (pinfunction "2_2") (pintype "bidirectional"))
      (node (ref "J5") (pin "2") (pinfunction "2_2") (pintype "passive"))
      (node (ref "J6") (pin "2") (pinfunction "2_2") (pintype "passive"))
      (node (ref "J7") (pin "2") (pinfunction "2_2") (pintype "passive"))
      (node (ref "V3") (pin "2") (pinfunction "2_2") (pintype "passive"))
    )
    (net (code "35") (name "VCC2-EXT") (class "Default")
      (node (ref "F2") (pin "2") (pinfunction "2_2") (pintype "bidirectional"))
      (node (ref "J3") (pin "2") (pinfunction "2_2") (pintype "passive"))
      (node (ref "J4") (pin "2") (pinfunction "2_2") (pintype "passive"))
      (node (ref "J8") (pin "2") (pinfunction "2_2") (pintype "passive"))
      (node (ref "J9") (pin "2") (pinfunction "2_2") (pintype "passive"))
      (node (ref "V2") (pin "2") (pinfunction "2_2") (pintype "passive"))
    )
    (net (code "36") (name "VUSB") (class "Default")
      (node (ref "C8") (pin "P$1") (pinfunction "P$1_P$1") (pintype "passive"))
      (node (ref "F1") (pin "2") (pinfunction "2_2") (pintype "bidirectional"))
      (node (ref "P1") (pin "VUSB") (pinfunction "VUSB_VUSB") (pintype "bidirectional"))
      (node (ref "V1") (pin "2") (pinfunction "2_2") (pintype "passive"))
    )
    (net (code "37") (name "WAKE") (class "Default")
      (node (ref "P1") (pin "D8") (pinfunction "D8_D8") (pintype "bidirectional"))
      (node (ref "U3") (pin "11") (pinfunction "FOUT/NIRQ_11") (pintype "output"))
    )
    (net (code "38") (name "unconnected-(P1-PadD5)") (class "Default")
      (node (ref "P1") (pin "D5") (pinfunction "D5_D5") (pintype "bidirectional"))
    )
    (net (code "39") (name "unconnected-(P1-PadD6)") (class "Default")
      (node (ref "P1") (pin "D6") (pinfunction "D6_D6") (pintype "bidirectional"))
    )
    (net (code "40") (name "unconnected-(P1-PadD7)") (class "Default")
      (node (ref "P1") (pin "D7") (pinfunction "D7_D7") (pintype "bidirectional"))
    )
    (net (code "41") (name "unconnected-(P1-PadMD)") (class "Default")
      (node (ref "P1") (pin "MD") (pinfunction "MD_MD") (pintype "bidirectional"))
    )
    (net (code "42") (name "unconnected-(P1-PadNC)") (class "Default")
      (node (ref "P1") (pin "NC") (pinfunction "NC_NC") (pintype "bidirectional"))
    )
    (net (code "43") (name "unconnected-(U1-NC-Pad3)") (class "Default")
      (node (ref "U1") (pin "3") (pinfunction "NC_3") (pintype "passive"))
    )
    (net (code "44") (name "unconnected-(U3-CLKOUT{slash}NIRQ3-Pad8)") (class "Default")
      (node (ref "U3") (pin "8") (pinfunction "CLKOUT/NIRQ3_8") (pintype "output"))
    )
    (net (code "45") (name "unconnected-(U3-NTIRQ-Pad12)") (class "Default")
      (node (ref "U3") (pin "12") (pinfunction "NTIRQ_12") (pintype "output"))
    )
    (net (code "46") (name "unconnected-(U6-NC-Pad4)") (class "Default")
      (node (ref "U6") (pin "4") (pinfunction "NC_4") (pintype "no_connect"))
    )
    (net (code "47") (name "~{RST}") (class "Default")
      (node (ref "P1") (pin "RST") (pinfunction "~{RST}_RST") (pintype "bidirectional"))
      (node (ref "U3") (pin "1") (pinfunction "NRST_1") (pintype "output"))
    )
  )
)
